# Adafruit_MICS-5524.net
KiCad netlist of a schematic drawn in EAGLE
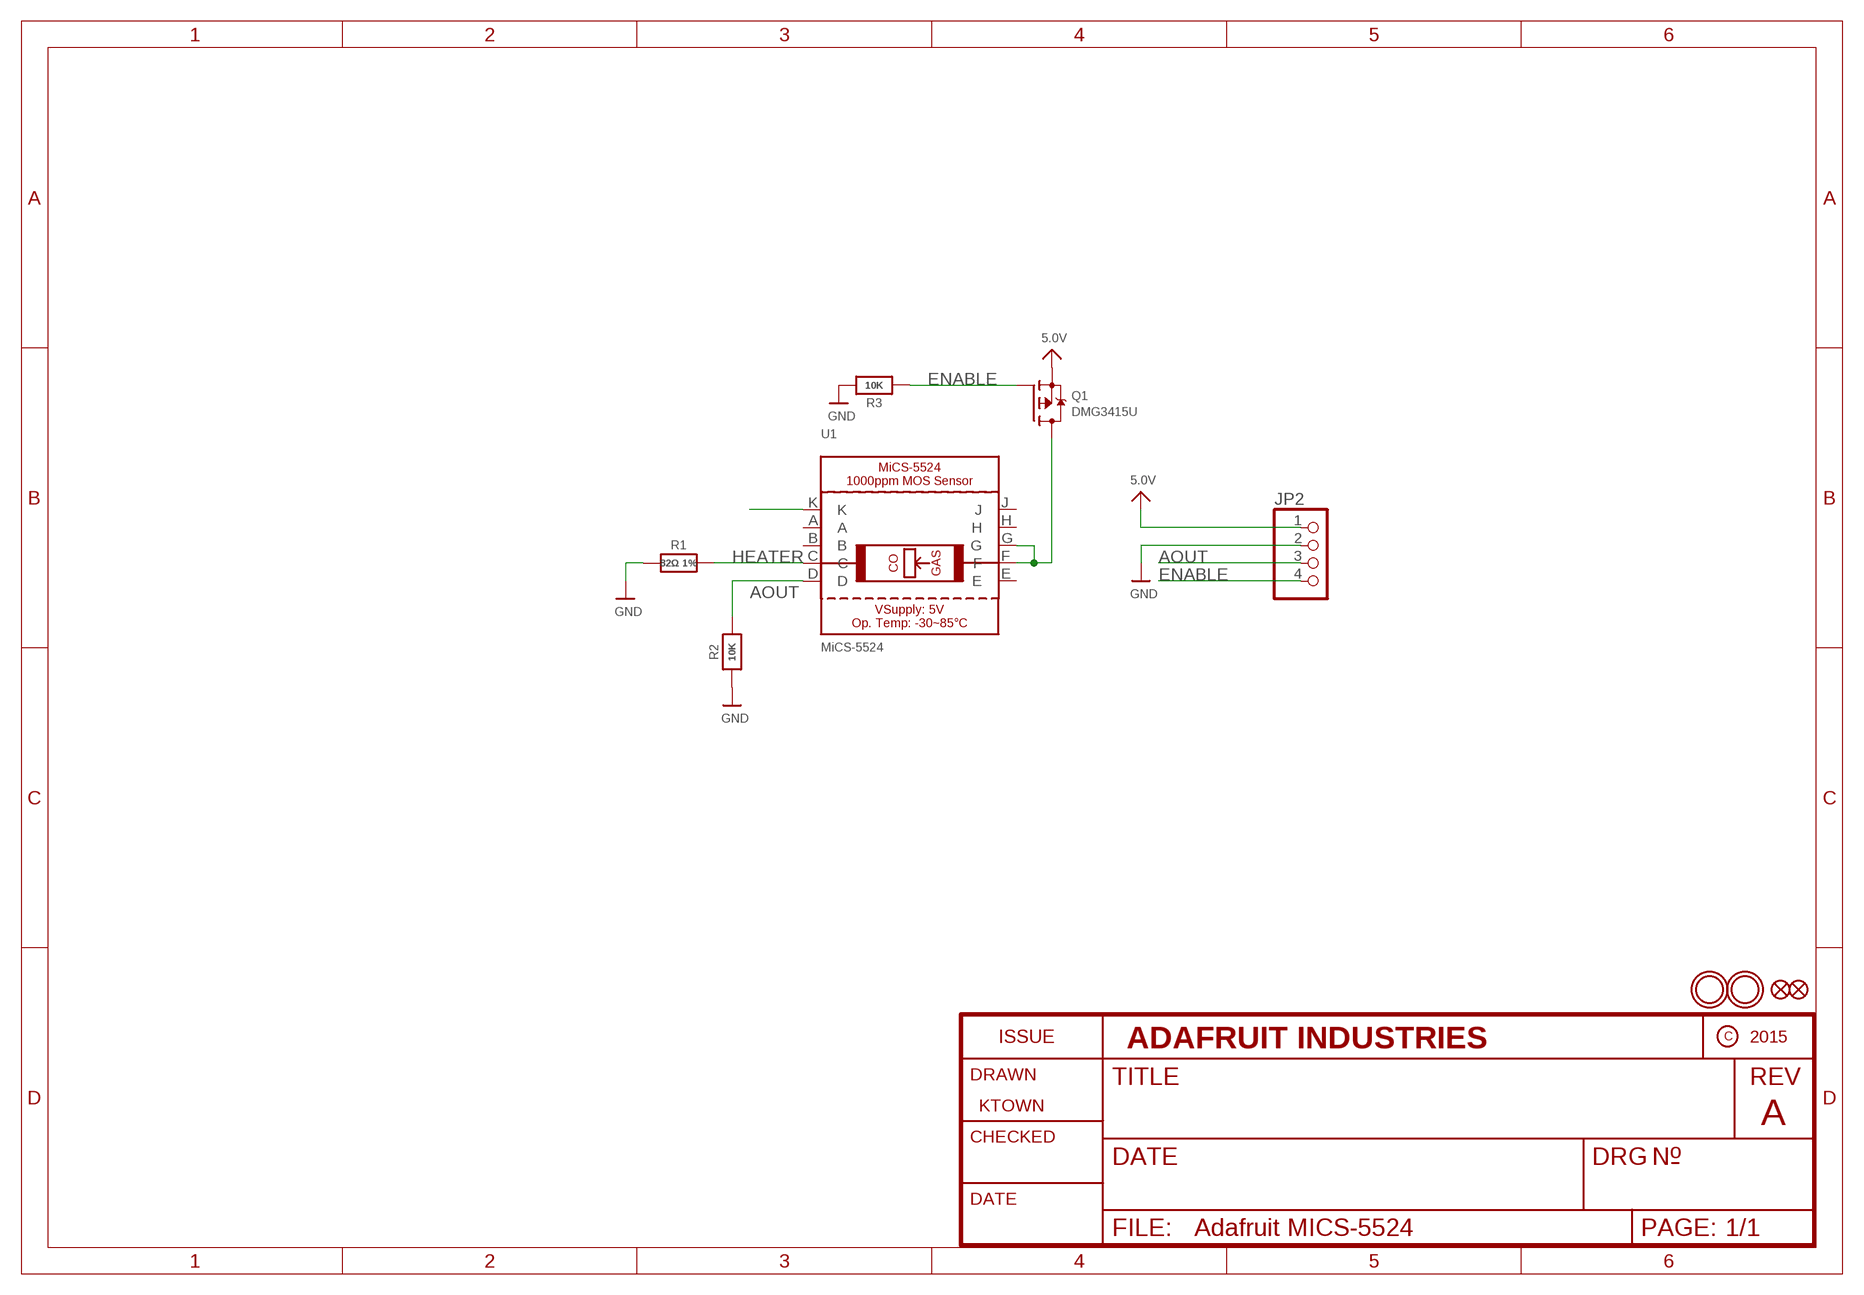
[diagram p0: schematic, sheet 1]

(export (version "E")
  (design (tool "Eeschema 10.0.6"))
  (components
    (comp (ref "FID1")
      (value "FIDUCIAL\"\"")
      (footprint "eagle-import:FIDUCIAL_1MM")
      (libsource (lib "eagle-import") (part "FIDUCIAL{dblquote}{dblquote}"))
    )
    (comp (ref "FID2")
      (value "FIDUCIAL\"\"")
      (footprint "eagle-import:FIDUCIAL_1MM")
      (libsource (lib "eagle-import") (part "FIDUCIAL{dblquote}{dblquote}"))
    )
    (comp (ref "JP2")
      (value "HEADER-1X476MIL")
      (footprint "eagle-import:1X04_ROUND_76")
      (libsource (lib "eagle-import") (part "HEADER-1X476MIL"))
    )
    (comp (ref "Q1")
      (value "DMG3415U")
      (footprint "eagle-import:SOT23-WIDE")
      (libsource (lib "eagle-import") (part "MOSFET-PWIDE"))
    )
    (comp (ref "R1")
      (value "82Ω 1%")
      (footprint "eagle-import:0805-NO")
      (libsource (lib "eagle-import") (part "RESISTOR0805_NOOUTLINE"))
    )
    (comp (ref "R2")
      (value "10K")
      (footprint "eagle-import:0805-NO")
      (libsource (lib "eagle-import") (part "RESISTOR0805_NOOUTLINE"))
    )
    (comp (ref "R3")
      (value "10K")
      (footprint "eagle-import:0805-NO")
      (libsource (lib "eagle-import") (part "RESISTOR0805_NOOUTLINE"))
    )
    (comp (ref "U$3")
      (value "MOUNTINGHOLE2.5")
      (footprint "eagle-import:MOUNTINGHOLE_2.5_PLATED")
      (libsource (lib "eagle-import") (part "MOUNTINGHOLE2.5"))
    )
    (comp (ref "U$4")
      (value "MOUNTINGHOLE2.5")
      (footprint "eagle-import:MOUNTINGHOLE_2.5_PLATED")
      (libsource (lib "eagle-import") (part "MOUNTINGHOLE2.5"))
    )
    (comp (ref "U1")
      (value "MiCS-5524")
      (footprint "eagle-import:MICS-5524")
      (libsource (lib "eagle-import") (part "MICS-5524"))
    )
  )
  (nets
    (net (code "1") (name "/AOUT") (class "Default")
      (node (ref "JP2") (pin "3") (pinfunction "3_3") (pintype "passive"))
      (node (ref "R2") (pin "2") (pinfunction "2_2") (pintype "passive"))
      (node (ref "U1") (pin "D") (pinfunction "D_D") (pintype "bidirectional"))
    )
    (net (code "2") (name "/ENABLE") (class "Default")
      (node (ref "JP2") (pin "4") (pinfunction "4_4") (pintype "passive"))
      (node (ref "Q1") (pin "1") (pinfunction "G_1") (pintype "passive"))
      (node (ref "R3") (pin "1") (pinfunction "1_1") (pintype "passive"))
    )
    (net (code "3") (name "/HEATER") (class "Default")
      (node (ref "R1") (pin "2") (pinfunction "2_2") (pintype "passive"))
      (node (ref "U1") (pin "C") (pinfunction "C_C") (pintype "bidirectional"))
    )
    (net (code "4") (name "5.0V") (class "Default")
      (node (ref "JP2") (pin "1") (pinfunction "1_1") (pintype "passive"))
      (node (ref "Q1") (pin "2") (pinfunction "S_2") (pintype "passive"))
    )
    (net (code "5") (name "GND") (class "Default")
      (node (ref "JP2") (pin "2") (pinfunction "2_2") (pintype "passive"))
      (node (ref "R1") (pin "1") (pinfunction "1_1") (pintype "passive"))
      (node (ref "R2") (pin "1") (pinfunction "1_1") (pintype "passive"))
      (node (ref "R3") (pin "2") (pinfunction "2_2") (pintype "passive"))
    )
    (net (code "6") (name "Net-(Q1-D)") (class "Default")
      (node (ref "Q1") (pin "3") (pinfunction "D_3") (pintype "passive"))
      (node (ref "U1") (pin "F") (pinfunction "F_F") (pintype "bidirectional"))
      (node (ref "U1") (pin "G") (pinfunction "G_G") (pintype "bidirectional"))
    )
    (net (code "7") (name "unconnected-(U1-PadA)") (class "Default")
      (node (ref "U1") (pin "A") (pinfunction "A_A") (pintype "bidirectional"))
    )
    (net (code "8") (name "unconnected-(U1-PadB)") (class "Default")
      (node (ref "U1") (pin "B") (pinfunction "B_B") (pintype "bidirectional"))
    )
    (net (code "9") (name "unconnected-(U1-PadE)") (class "Default")
      (node (ref "U1") (pin "E") (pinfunction "E_E") (pintype "bidirectional"))
    )
    (net (code "10") (name "unconnected-(U1-PadH)") (class "Default")
      (node (ref "U1") (pin "H") (pinfunction "H_H") (pintype "bidirectional"))
    )
    (net (code "11") (name "unconnected-(U1-PadJ)") (class "Default")
      (node (ref "U1") (pin "J") (pinfunction "J_J") (pintype "bidirectional"))
    )
    (net (code "12") (name "unconnected-(U1-PadK)") (class "Default")
      (node (ref "U1") (pin "K") (pinfunction "K_K") (pintype "bidirectional"))
    )
  )
)
